# eElements.net
KiCad netlist of a schematic drawn in Altium Designer
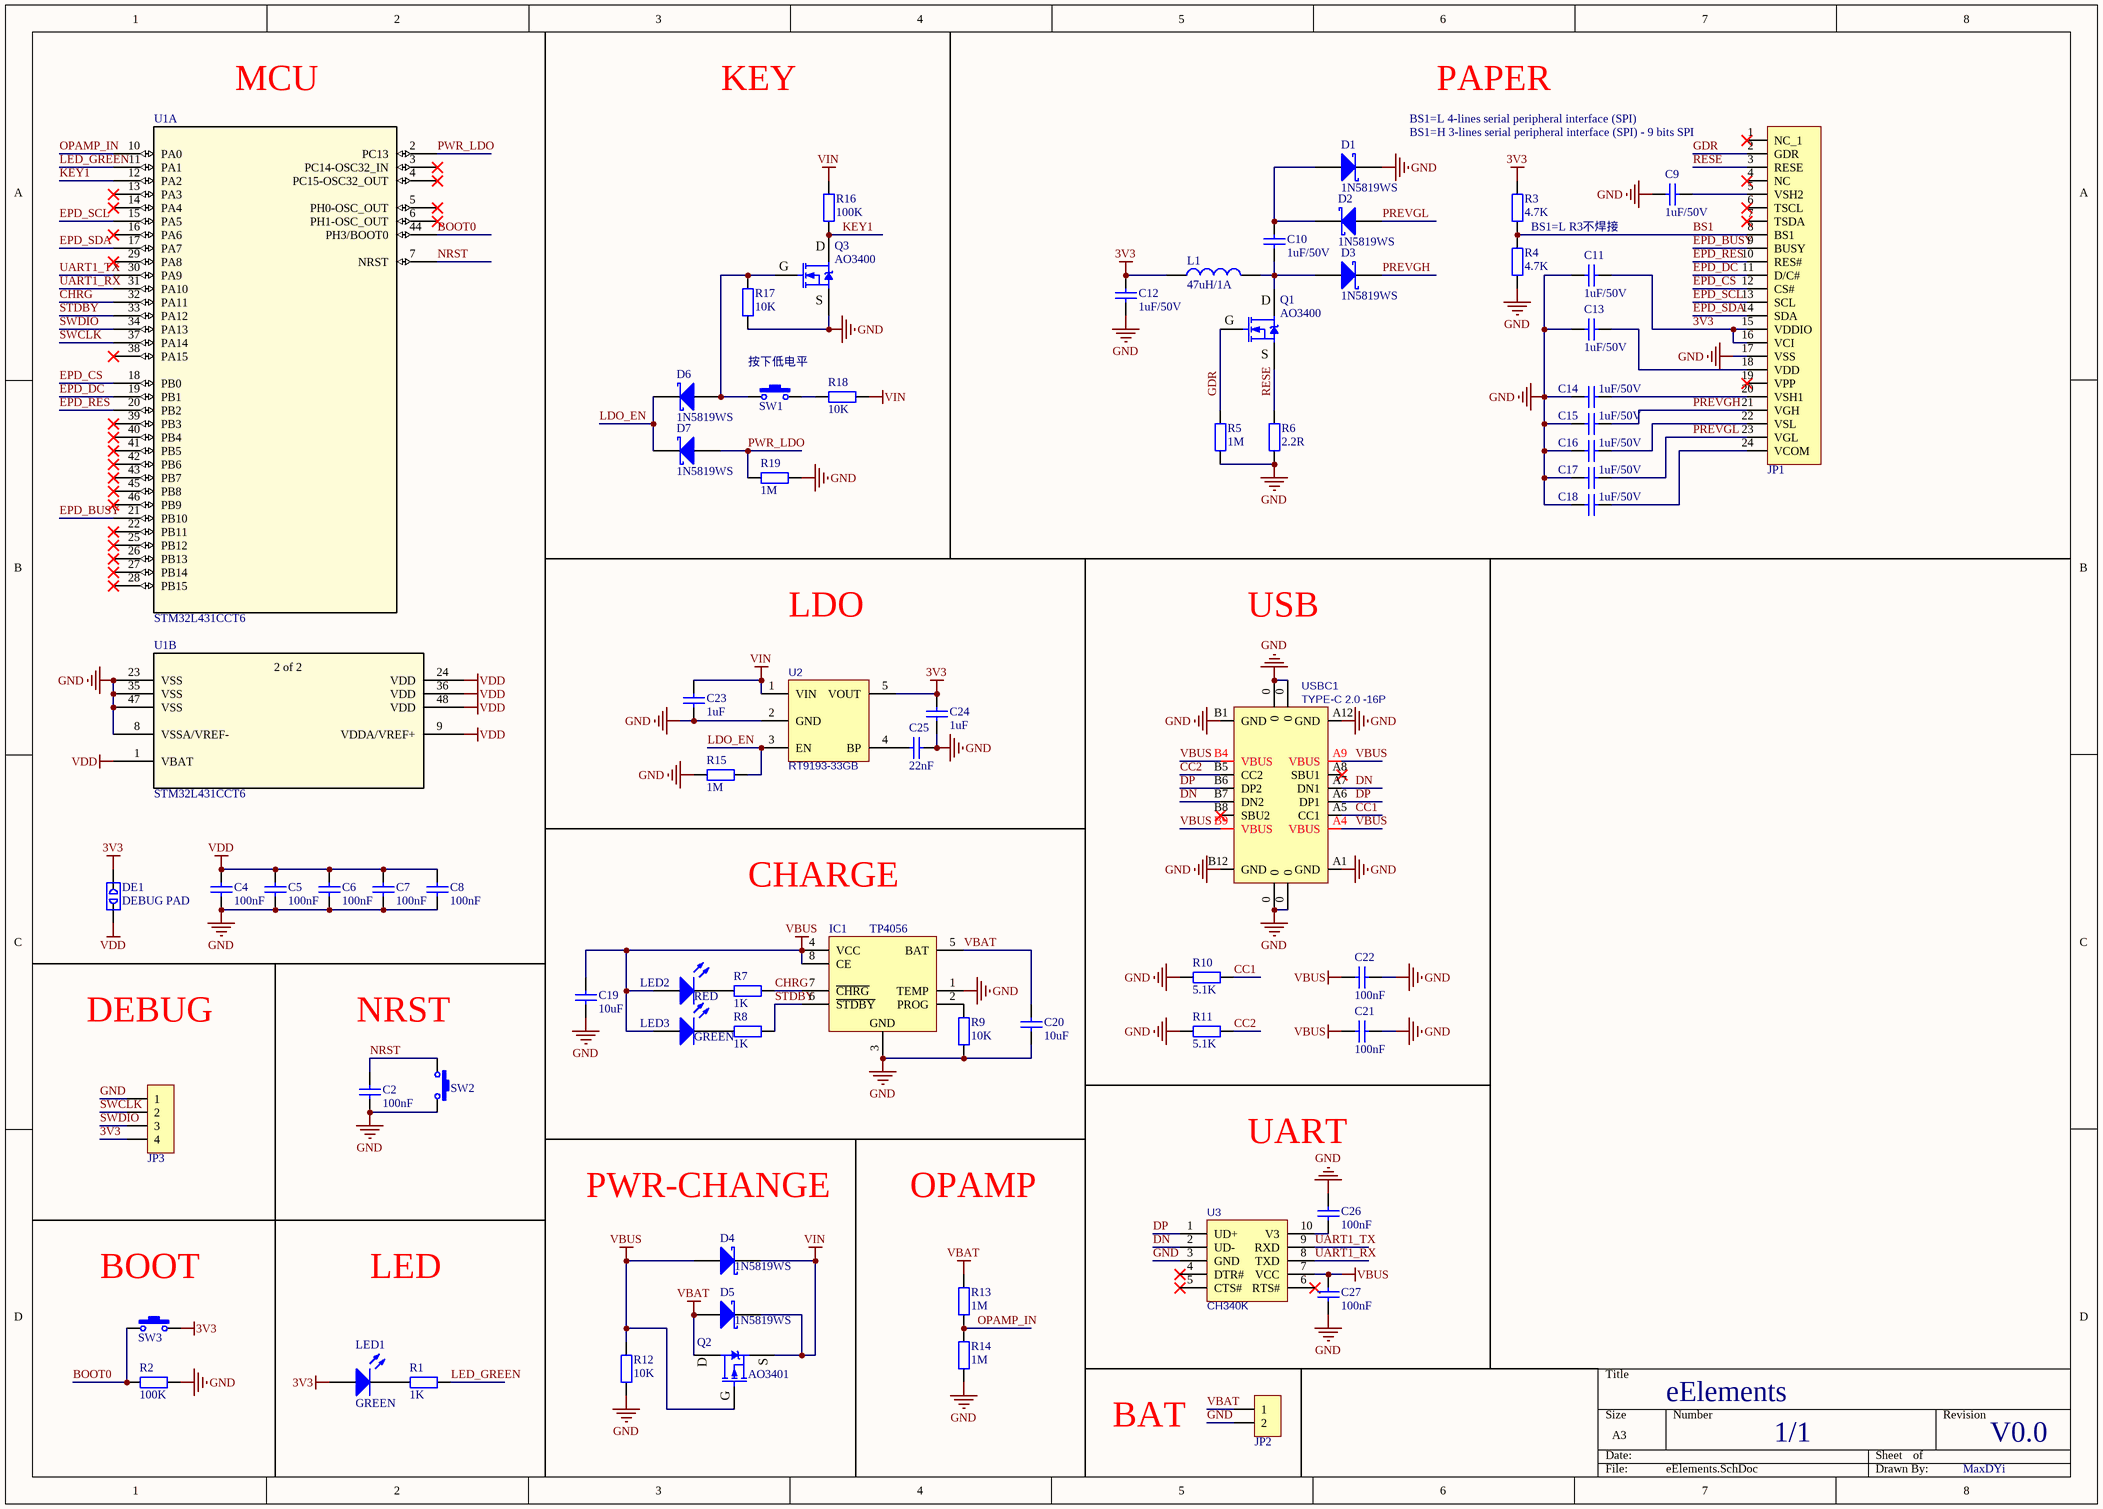
[diagram p0: eElements.SchDoc]

(export (version "E")
  (design (tool "Eeschema 10.0.6"))
  (components
    (comp (ref "C2")
      (value "100nF")
      (footprint "C0402_M")
      (description "贴片电容/MLCC电容")
      (libsource (lib "0.1 - 电阻-电容-电感-保险丝-晶振-晶体-磁珠-电位器-法拉电容-馈通电容") (part "C"))
    )
    (comp (ref "C4")
      (value "100nF")
      (footprint "C0402_M")
      (description "贴片电容/MLCC电容")
      (libsource (lib "0.1 - 电阻-电容-电感-保险丝-晶振-晶体-磁珠-电位器-法拉电容-馈通电容") (part "C"))
    )
    (comp (ref "C5")
      (value "100nF")
      (footprint "C0402_M")
      (description "贴片电容/MLCC电容")
      (libsource (lib "0.1 - 电阻-电容-电感-保险丝-晶振-晶体-磁珠-电位器-法拉电容-馈通电容") (part "C"))
    )
    (comp (ref "C6")
      (value "100nF")
      (footprint "C0402_M")
      (description "贴片电容/MLCC电容")
      (libsource (lib "0.1 - 电阻-电容-电感-保险丝-晶振-晶体-磁珠-电位器-法拉电容-馈通电容") (part "C"))
    )
    (comp (ref "C7")
      (value "100nF")
      (footprint "C0402_M")
      (description "贴片电容/MLCC电容")
      (libsource (lib "0.1 - 电阻-电容-电感-保险丝-晶振-晶体-磁珠-电位器-法拉电容-馈通电容") (part "C"))
    )
    (comp (ref "C8")
      (value "100nF")
      (footprint "C0402_M")
      (description "贴片电容/MLCC电容")
      (libsource (lib "0.1 - 电阻-电容-电感-保险丝-晶振-晶体-磁珠-电位器-法拉电容-馈通电容") (part "C"))
    )
    (comp (ref "C9")
      (value "1uF/50V")
      (footprint "C0402_M")
      (description "贴片电容/MLCC电容")
      (libsource (lib "0.1 - 电阻-电容-电感-保险丝-晶振-晶体-磁珠-电位器-法拉电容-馈通电容") (part "C"))
    )
    (comp (ref "C10")
      (value "1uF/50V")
      (footprint "C0402_M")
      (description "贴片电容/MLCC电容")
      (libsource (lib "0.1 - 电阻-电容-电感-保险丝-晶振-晶体-磁珠-电位器-法拉电容-馈通电容") (part "C"))
    )
    (comp (ref "C11")
      (value "1uF/50V")
      (footprint "C0402_M")
      (description "贴片电容/MLCC电容")
      (libsource (lib "0.1 - 电阻-电容-电感-保险丝-晶振-晶体-磁珠-电位器-法拉电容-馈通电容") (part "C"))
    )
    (comp (ref "C12")
      (value "1uF/50V")
      (footprint "C0402_M")
      (description "贴片电容/MLCC电容")
      (libsource (lib "0.1 - 电阻-电容-电感-保险丝-晶振-晶体-磁珠-电位器-法拉电容-馈通电容") (part "C"))
    )
    (comp (ref "C13")
      (value "1uF/50V")
      (footprint "C0402_M")
      (description "贴片电容/MLCC电容")
      (libsource (lib "0.1 - 电阻-电容-电感-保险丝-晶振-晶体-磁珠-电位器-法拉电容-馈通电容") (part "C"))
    )
    (comp (ref "C14")
      (value "1uF/50V")
      (footprint "C0402_M")
      (description "贴片电容/MLCC电容")
      (libsource (lib "0.1 - 电阻-电容-电感-保险丝-晶振-晶体-磁珠-电位器-法拉电容-馈通电容") (part "C"))
    )
    (comp (ref "C15")
      (value "1uF/50V")
      (footprint "C0402_M")
      (description "贴片电容/MLCC电容")
      (libsource (lib "0.1 - 电阻-电容-电感-保险丝-晶振-晶体-磁珠-电位器-法拉电容-馈通电容") (part "C"))
    )
    (comp (ref "C16")
      (value "1uF/50V")
      (footprint "C0402_M")
      (description "贴片电容/MLCC电容")
      (libsource (lib "0.1 - 电阻-电容-电感-保险丝-晶振-晶体-磁珠-电位器-法拉电容-馈通电容") (part "C"))
    )
    (comp (ref "C17")
      (value "1uF/50V")
      (footprint "C0402_M")
      (description "贴片电容/MLCC电容")
      (libsource (lib "0.1 - 电阻-电容-电感-保险丝-晶振-晶体-磁珠-电位器-法拉电容-馈通电容") (part "C"))
    )
    (comp (ref "C18")
      (value "1uF/50V")
      (footprint "C0402_M")
      (description "贴片电容/MLCC电容")
      (libsource (lib "0.1 - 电阻-电容-电感-保险丝-晶振-晶体-磁珠-电位器-法拉电容-馈通电容") (part "C"))
    )
    (comp (ref "C19")
      (value "10uF")
      (footprint "C0402_M")
      (description "贴片电容/MLCC电容")
      (libsource (lib "0.1 - 电阻-电容-电感-保险丝-晶振-晶体-磁珠-电位器-法拉电容-馈通电容") (part "C"))
    )
    (comp (ref "C20")
      (value "10uF")
      (footprint "C0402_M")
      (description "贴片电容/MLCC电容")
      (libsource (lib "0.1 - 电阻-电容-电感-保险丝-晶振-晶体-磁珠-电位器-法拉电容-馈通电容") (part "C"))
    )
    (comp (ref "C21")
      (value "100nF")
      (footprint "C0402_M")
      (description "贴片电容/MLCC电容")
      (libsource (lib "0.1 - 电阻-电容-电感-保险丝-晶振-晶体-磁珠-电位器-法拉电容-馈通电容") (part "C"))
    )
    (comp (ref "C22")
      (value "100nF")
      (footprint "C0402_M")
      (description "贴片电容/MLCC电容")
      (libsource (lib "0.1 - 电阻-电容-电感-保险丝-晶振-晶体-磁珠-电位器-法拉电容-馈通电容") (part "C"))
    )
    (comp (ref "C23")
      (value "1uF")
      (footprint "C0402_M")
      (description "贴片电容/MLCC电容")
      (libsource (lib "0.1 - 电阻-电容-电感-保险丝-晶振-晶体-磁珠-电位器-法拉电容-馈通电容") (part "C"))
    )
    (comp (ref "C24")
      (value "1uF")
      (footprint "C0402_M")
      (description "贴片电容/MLCC电容")
      (libsource (lib "0.1 - 电阻-电容-电感-保险丝-晶振-晶体-磁珠-电位器-法拉电容-馈通电容") (part "C"))
    )
    (comp (ref "C25")
      (value "22nF")
      (footprint "C0402_M")
      (description "贴片电容/MLCC电容")
      (libsource (lib "0.1 - 电阻-电容-电感-保险丝-晶振-晶体-磁珠-电位器-法拉电容-馈通电容") (part "C"))
    )
    (comp (ref "C26")
      (value "100nF")
      (footprint "C0402_M")
      (description "贴片电容/MLCC电容")
      (libsource (lib "0.1 - 电阻-电容-电感-保险丝-晶振-晶体-磁珠-电位器-法拉电容-馈通电容") (part "C"))
    )
    (comp (ref "C27")
      (value "100nF")
      (footprint "C0402_M")
      (description "贴片电容/MLCC电容")
      (libsource (lib "0.1 - 电阻-电容-电感-保险丝-晶振-晶体-磁珠-电位器-法拉电容-馈通电容") (part "C"))
    )
    (comp (ref "D1")
      (value "1N5819WS")
      (footprint "SOD-323")
      (description "肖特基二极管")
      (libsource (lib "0.2 - 二极管-TVS-ESD-整流桥-放电管") (part "1N5819"))
    )
    (comp (ref "D2")
      (value "1N5819WS")
      (footprint "SOD-323")
      (description "肖特基二极管")
      (libsource (lib "0.2 - 二极管-TVS-ESD-整流桥-放电管") (part "1N5819"))
    )
    (comp (ref "D3")
      (value "1N5819WS")
      (footprint "SOD-323")
      (description "肖特基二极管")
      (libsource (lib "0.2 - 二极管-TVS-ESD-整流桥-放电管") (part "1N5819"))
    )
    (comp (ref "D4")
      (value "1N5819WS")
      (footprint "SOD-323")
      (description "肖特基二极管")
      (libsource (lib "0.2 - 二极管-TVS-ESD-整流桥-放电管") (part "1N5819"))
    )
    (comp (ref "D5")
      (value "1N5819WS")
      (footprint "SOD-323")
      (description "肖特基二极管")
      (libsource (lib "0.2 - 二极管-TVS-ESD-整流桥-放电管") (part "1N5819"))
    )
    (comp (ref "D6")
      (value "1N5819WS")
      (footprint "SOD-323")
      (description "肖特基二极管")
      (libsource (lib "0.2 - 二极管-TVS-ESD-整流桥-放电管") (part "1N5819"))
    )
    (comp (ref "D7")
      (value "1N5819WS")
      (footprint "SOD-323")
      (description "肖特基二极管")
      (libsource (lib "0.2 - 二极管-TVS-ESD-整流桥-放电管") (part "1N5819"))
    )
    (comp (ref "DE1")
      (value "DEBUG PAD")
      (footprint "DEBUG_B")
      (description "调试断点焊盘")
      (libsource (lib "0.5 - 按键_开关_蜂鸣器_电池_测试点_Mark点_铜柱") (part "DEBUG"))
    )
    (comp (ref "IC1")
      (value "TP4056")
      (footprint "SOIC-8_EP")
      (description "锂电池充电管理")
      (libsource (lib "0.7 - 电源类芯片") (part "TP4056"))
    )
    (comp (ref "JP1")
      (value "CON-24P")
      (footprint "FPC0.5-WT-24P-上接")
      (description "2.54寸墨水屏24P连接器（上接点或上下接点24PIN的0.5mmFPC插座）")
      (libsource (lib "0.9 - 传感器-存储器-模块") (part "EPD-1.54"))
    )
    (comp (ref "JP2")
      (value "HDR-1X2")
      (footprint "MX1.25-W-2P")
      (description "2P连接器")
      (libsource (lib "5.1 - 1.25mm连接器(FPC1.25_GH1.25_MX1.25)") (part "Header 2"))
    )
    (comp (ref "JP3")
      (value "HDR-1X4")
      (footprint "HDR1.27-LI-4P")
      (description "4P连接器")
      (libsource (lib "5.2 - 1.27mm连接器(1.27排针排母)") (part "Header 4"))
    )
    (comp (ref "L1")
      (value "47uH/1A")
      (footprint "SWPA4030")
      (description "贴片小功率电感")
      (libsource (lib "0.1 - 电阻-电容-电感-保险丝-晶振-晶体-磁珠-电位器-法拉电容-馈通电容") (part "L"))
    )
    (comp (ref "LED1")
      (value "GREEN")
      (footprint "LED0603_R")
      (description "贴片LED")
      (libsource (lib "0.3 - LED发光二极管-IR二极管_接收管-光耦") (part "LED"))
    )
    (comp (ref "LED2")
      (value "RED")
      (footprint "LED0603_R")
      (description "贴片LED")
      (libsource (lib "0.3 - LED发光二极管-IR二极管_接收管-光耦") (part "LED"))
    )
    (comp (ref "LED3")
      (value "GREEN")
      (footprint "LED0603_R")
      (description "贴片LED")
      (libsource (lib "0.3 - LED发光二极管-IR二极管_接收管-光耦") (part "LED"))
    )
    (comp (ref "Q1")
      (value "AO3400")
      (footprint "SOT23-3N")
      (description "N沟道 30V/4.2A")
      (libsource (lib "0.4 - 三极管-场效应管-可控硅") (part "AO3400"))
    )
    (comp (ref "Q2")
      (value "AO3401")
      (footprint "SOT23-3N")
      (description "P沟道 30V/4.2A")
      (libsource (lib "0.4 - 三极管-场效应管-可控硅") (part "AO3401"))
    )
    (comp (ref "Q3")
      (value "AO3400")
      (footprint "SOT23-3N")
      (description "N沟道 30V/4.2A")
      (libsource (lib "0.4 - 三极管-场效应管-可控硅") (part "AO3400"))
    )
    (comp (ref "R1")
      (value "1K")
      (footprint "R0402_M")
      (description "贴片电阻")
      (libsource (lib "0.1 - 电阻-电容-电感-保险丝-晶振-晶体-磁珠-电位器-法拉电容-馈通电容") (part "R"))
    )
    (comp (ref "R2")
      (value "100K")
      (footprint "R0402_M")
      (description "贴片电阻")
      (libsource (lib "0.1 - 电阻-电容-电感-保险丝-晶振-晶体-磁珠-电位器-法拉电容-馈通电容") (part "R"))
    )
    (comp (ref "R3")
      (value "4.7K")
      (footprint "R0402_M")
      (description "贴片电阻")
      (libsource (lib "0.1 - 电阻-电容-电感-保险丝-晶振-晶体-磁珠-电位器-法拉电容-馈通电容") (part "R"))
    )
    (comp (ref "R4")
      (value "4.7K")
      (footprint "R0402_M")
      (description "贴片电阻")
      (libsource (lib "0.1 - 电阻-电容-电感-保险丝-晶振-晶体-磁珠-电位器-法拉电容-馈通电容") (part "R"))
    )
    (comp (ref "R5")
      (value "1M")
      (footprint "R0402_M")
      (description "贴片电阻")
      (libsource (lib "0.1 - 电阻-电容-电感-保险丝-晶振-晶体-磁珠-电位器-法拉电容-馈通电容") (part "R"))
    )
    (comp (ref "R6")
      (value "2.2R")
      (footprint "R0603_M")
      (description "贴片电阻")
      (libsource (lib "0.1 - 电阻-电容-电感-保险丝-晶振-晶体-磁珠-电位器-法拉电容-馈通电容") (part "R"))
    )
    (comp (ref "R7")
      (value "1K")
      (footprint "R0402_M")
      (description "贴片电阻")
      (libsource (lib "0.1 - 电阻-电容-电感-保险丝-晶振-晶体-磁珠-电位器-法拉电容-馈通电容") (part "R"))
    )
    (comp (ref "R8")
      (value "1K")
      (footprint "R0402_M")
      (description "贴片电阻")
      (libsource (lib "0.1 - 电阻-电容-电感-保险丝-晶振-晶体-磁珠-电位器-法拉电容-馈通电容") (part "R"))
    )
    (comp (ref "R9")
      (value "10K")
      (footprint "R0402_M")
      (description "贴片电阻")
      (libsource (lib "0.1 - 电阻-电容-电感-保险丝-晶振-晶体-磁珠-电位器-法拉电容-馈通电容") (part "R"))
    )
    (comp (ref "R10")
      (value "5.1K")
      (footprint "R0402_M")
      (description "贴片电阻")
      (libsource (lib "0.1 - 电阻-电容-电感-保险丝-晶振-晶体-磁珠-电位器-法拉电容-馈通电容") (part "R"))
    )
    (comp (ref "R11")
      (value "5.1K")
      (footprint "R0402_M")
      (description "贴片电阻")
      (libsource (lib "0.1 - 电阻-电容-电感-保险丝-晶振-晶体-磁珠-电位器-法拉电容-馈通电容") (part "R"))
    )
    (comp (ref "R12")
      (value "10K")
      (footprint "R0402_M")
      (description "贴片电阻")
      (libsource (lib "0.1 - 电阻-电容-电感-保险丝-晶振-晶体-磁珠-电位器-法拉电容-馈通电容") (part "R"))
    )
    (comp (ref "R13")
      (value "1M")
      (footprint "R0402_M")
      (description "贴片电阻")
      (libsource (lib "0.1 - 电阻-电容-电感-保险丝-晶振-晶体-磁珠-电位器-法拉电容-馈通电容") (part "R"))
    )
    (comp (ref "R14")
      (value "1M")
      (footprint "R0402_M")
      (description "贴片电阻")
      (libsource (lib "0.1 - 电阻-电容-电感-保险丝-晶振-晶体-磁珠-电位器-法拉电容-馈通电容") (part "R"))
    )
    (comp (ref "R15")
      (value "1M")
      (footprint "R0402_M")
      (description "贴片电阻")
      (libsource (lib "0.1 - 电阻-电容-电感-保险丝-晶振-晶体-磁珠-电位器-法拉电容-馈通电容") (part "R"))
    )
    (comp (ref "R16")
      (value "100K")
      (footprint "R0402_M")
      (description "贴片电阻")
      (libsource (lib "0.1 - 电阻-电容-电感-保险丝-晶振-晶体-磁珠-电位器-法拉电容-馈通电容") (part "R"))
    )
    (comp (ref "R17")
      (value "10K")
      (footprint "R0402_M")
      (description "贴片电阻")
      (libsource (lib "0.1 - 电阻-电容-电感-保险丝-晶振-晶体-磁珠-电位器-法拉电容-馈通电容") (part "R"))
    )
    (comp (ref "R18")
      (value "10K")
      (footprint "R0402_M")
      (description "贴片电阻")
      (libsource (lib "0.1 - 电阻-电容-电感-保险丝-晶振-晶体-磁珠-电位器-法拉电容-馈通电容") (part "R"))
    )
    (comp (ref "R19")
      (value "1M")
      (footprint "R0402_M")
      (description "贴片电阻")
      (libsource (lib "0.1 - 电阻-电容-电感-保险丝-晶振-晶体-磁珠-电位器-法拉电容-馈通电容") (part "R"))
    )
    (comp (ref "SW1")
      (value "3x6x5")
      (footprint "SW 3*6*4.3-S-W")
      (description "微动开关")
      (libsource (lib "0.5 - 按键_开关_蜂鸣器_电池_测试点_Mark点_铜柱") (part "SW-PB"))
    )
    (comp (ref "SW2")
      (value "3x6x5")
      (footprint "SW SMD-3*6*2.5")
      (description "微动开关")
      (libsource (lib "0.5 - 按键_开关_蜂鸣器_电池_测试点_Mark点_铜柱") (part "SW-PB"))
    )
    (comp (ref "SW3")
      (value "3x6x5")
      (footprint "SW SMD-3*6*2.5")
      (description "微动开关")
      (libsource (lib "0.5 - 按键_开关_蜂鸣器_电池_测试点_Mark点_铜柱") (part "SW-PB"))
    )
    (comp (ref "U1")
      (value "STM32L431CCT6")
      (footprint "LQFP48_M")
      (description "Ultra-low-power with FPU Arm Cortex-M4 MCU 80 MHz with 256 Kbytes of Flash memory")
      (libsource (lib "3.0 - STM32L0-L1-L4系列单片机") (part "STM32L431CCT6"))
    )
    (comp (ref "U2")
      (value "RT9193-33GB")
      (footprint "SOT-23-5")
      (description "LDO 3.3V/0.3A")
      (libsource (lib "0.7 - 电源类芯片") (part "RT9193-33GB"))
    )
    (comp (ref "U3")
      (value "CH340K")
      (footprint "SOP10_M")
      (description "USB转串口芯片, 内置晶振")
      (libsource (lib "0.8 - 常见芯片") (part "CH340K"))
    )
    (comp (ref "USBC1")
      (value "TYPE-C 2.0 -16P")
      (footprint "USB-C-SMD_16P")
      (description "USB2.0_Type-C_16Pin母座")
      (libsource (lib "0.6 - 电源_音频_USB Type-C_HDMI_XT60_5557_D-SUB_RJ45_SD-TF_SIM插座") (part "USB2.0_Type-C_16Pin"))
    )
  )
  (nets
    (net (code "1") (name "/BOOT0") (class "Default")
      (node (ref "R2") (pin "1") (pinfunction "1_1") (pintype "passive"))
      (node (ref "SW3") (pin "1") (pinfunction "1_1") (pintype "passive"))
      (node (ref "U1") (pin "44") (pinfunction "PH3/BOOT0_44") (pintype "bidirectional"))
    )
    (net (code "2") (name "/BS1") (class "Default")
      (node (ref "JP1") (pin "8") (pinfunction "BS1_8") (pintype "passive"))
      (node (ref "R3") (pin "1") (pinfunction "1_1") (pintype "passive"))
      (node (ref "R4") (pin "2") (pinfunction "2_2") (pintype "passive"))
    )
    (net (code "3") (name "/CC1") (class "Default")
      (node (ref "R10") (pin "1") (pinfunction "1_1") (pintype "passive"))
      (node (ref "USBC1") (pin "A5") (pinfunction "CC1_A5") (pintype "passive"))
    )
    (net (code "4") (name "/CC2") (class "Default")
      (node (ref "R11") (pin "1") (pinfunction "1_1") (pintype "passive"))
      (node (ref "USBC1") (pin "B5") (pinfunction "CC2_B5") (pintype "passive"))
    )
    (net (code "5") (name "/CHRG") (class "Default")
      (node (ref "IC1") (pin "7") (pinfunction "~{CHRG}_7") (pintype "passive"))
      (node (ref "R7") (pin "1") (pinfunction "1_1") (pintype "passive"))
      (node (ref "U1") (pin "32") (pinfunction "PA11_32") (pintype "bidirectional"))
    )
    (net (code "6") (name "/DN") (class "Default")
      (node (ref "U3") (pin "2") (pinfunction "UD-_2") (pintype "passive"))
      (node (ref "USBC1") (pin "A7") (pinfunction "DN1_A7") (pintype "passive"))
      (node (ref "USBC1") (pin "B7") (pinfunction "DN2_B7") (pintype "passive"))
    )
    (net (code "7") (name "/DP") (class "Default")
      (node (ref "U3") (pin "1") (pinfunction "UD+_1") (pintype "passive"))
      (node (ref "USBC1") (pin "A6") (pinfunction "DP1_A6") (pintype "passive"))
      (node (ref "USBC1") (pin "B6") (pinfunction "DP2_B6") (pintype "passive"))
    )
    (net (code "8") (name "/EPD_BUSY") (class "Default")
      (node (ref "JP1") (pin "9") (pinfunction "BUSY_9") (pintype "passive"))
      (node (ref "U1") (pin "21") (pinfunction "PB10_21") (pintype "bidirectional"))
    )
    (net (code "9") (name "/EPD_CS") (class "Default")
      (node (ref "JP1") (pin "12") (pinfunction "CS#_12") (pintype "passive"))
      (node (ref "U1") (pin "18") (pinfunction "PB0_18") (pintype "bidirectional"))
    )
    (net (code "10") (name "/EPD_DC") (class "Default")
      (node (ref "JP1") (pin "11") (pinfunction "D/C#_11") (pintype "passive"))
      (node (ref "U1") (pin "19") (pinfunction "PB1_19") (pintype "bidirectional"))
    )
    (net (code "11") (name "/EPD_RES") (class "Default")
      (node (ref "JP1") (pin "10") (pinfunction "RES#_10") (pintype "passive"))
      (node (ref "U1") (pin "20") (pinfunction "PB2_20") (pintype "bidirectional"))
    )
    (net (code "12") (name "/EPD_SCL") (class "Default")
      (node (ref "JP1") (pin "13") (pinfunction "SCL_13") (pintype "passive"))
      (node (ref "U1") (pin "15") (pinfunction "PA5_15") (pintype "bidirectional"))
    )
    (net (code "13") (name "/EPD_SDA") (class "Default")
      (node (ref "JP1") (pin "14") (pinfunction "SDA_14") (pintype "passive"))
      (node (ref "U1") (pin "17") (pinfunction "PA7_17") (pintype "bidirectional"))
    )
    (net (code "14") (name "/GDR") (class "Default")
      (node (ref "JP1") (pin "2") (pinfunction "GDR_2") (pintype "passive"))
      (node (ref "Q1") (pin "1") (pinfunction "G_1") (pintype "passive"))
      (node (ref "R5") (pin "2") (pinfunction "2_2") (pintype "passive"))
    )
    (net (code "15") (name "/KEY1") (class "Default")
      (node (ref "Q3") (pin "3") (pinfunction "D_3") (pintype "passive"))
      (node (ref "R16") (pin "1") (pinfunction "1_1") (pintype "passive"))
      (node (ref "U1") (pin "12") (pinfunction "PA2_12") (pintype "bidirectional"))
    )
    (net (code "16") (name "/LDO_EN") (class "Default")
      (node (ref "D6") (pin "2") (pinfunction "K_2") (pintype "passive"))
      (node (ref "D7") (pin "2") (pinfunction "K_2") (pintype "passive"))
      (node (ref "R15") (pin "1") (pinfunction "1_1") (pintype "passive"))
      (node (ref "U2") (pin "3") (pinfunction "EN_3") (pintype "passive"))
    )
    (net (code "17") (name "/LED_GREEN") (class "Default")
      (node (ref "R1") (pin "1") (pinfunction "1_1") (pintype "passive"))
      (node (ref "U1") (pin "11") (pinfunction "PA1_11") (pintype "bidirectional"))
    )
    (net (code "18") (name "/NRST") (class "Default")
      (node (ref "C2") (pin "2") (pinfunction "2_2") (pintype "passive"))
      (node (ref "SW2") (pin "1") (pinfunction "1_1") (pintype "passive"))
      (node (ref "U1") (pin "7") (pinfunction "NRST_7") (pintype "bidirectional"))
    )
    (net (code "19") (name "/OPAMP_IN") (class "Default")
      (node (ref "R13") (pin "1") (pinfunction "1_1") (pintype "passive"))
      (node (ref "R14") (pin "2") (pinfunction "2_2") (pintype "passive"))
      (node (ref "U1") (pin "10") (pinfunction "PA0_10") (pintype "bidirectional"))
    )
    (net (code "20") (name "/PREVGH") (class "Default")
      (node (ref "C15") (pin "2") (pinfunction "2_2") (pintype "passive"))
      (node (ref "D3") (pin "2") (pinfunction "K_2") (pintype "passive"))
      (node (ref "JP1") (pin "21") (pinfunction "VGH_21") (pintype "passive"))
    )
    (net (code "21") (name "/PREVGL") (class "Default")
      (node (ref "C17") (pin "2") (pinfunction "2_2") (pintype "passive"))
      (node (ref "D2") (pin "1") (pinfunction "A_1") (pintype "passive"))
      (node (ref "JP1") (pin "23") (pinfunction "VGL_23") (pintype "passive"))
    )
    (net (code "22") (name "/PWR_LDO") (class "Default")
      (node (ref "D7") (pin "1") (pinfunction "A_1") (pintype "passive"))
      (node (ref "R19") (pin "2") (pinfunction "2_2") (pintype "passive"))
      (node (ref "U1") (pin "2") (pinfunction "PC13_2") (pintype "bidirectional"))
    )
    (net (code "23") (name "/RESE") (class "Default")
      (node (ref "JP1") (pin "3") (pinfunction "RESE_3") (pintype "passive"))
      (node (ref "Q1") (pin "2") (pinfunction "S_2") (pintype "passive"))
      (node (ref "R6") (pin "2") (pinfunction "2_2") (pintype "passive"))
    )
    (net (code "24") (name "/STDBY") (class "Default")
      (node (ref "IC1") (pin "6") (pinfunction "~{STDBY}_6") (pintype "passive"))
      (node (ref "R8") (pin "1") (pinfunction "1_1") (pintype "passive"))
      (node (ref "U1") (pin "33") (pinfunction "PA12_33") (pintype "bidirectional"))
    )
    (net (code "25") (name "/SWCLK") (class "Default")
      (node (ref "JP3") (pin "2") (pinfunction "2_2") (pintype "passive"))
      (node (ref "U1") (pin "37") (pinfunction "PA14_37") (pintype "bidirectional"))
    )
    (net (code "26") (name "/SWDIO") (class "Default")
      (node (ref "JP3") (pin "3") (pinfunction "3_3") (pintype "passive"))
      (node (ref "U1") (pin "34") (pinfunction "PA13_34") (pintype "bidirectional"))
    )
    (net (code "27") (name "/UART1_RX") (class "Default")
      (node (ref "U1") (pin "31") (pinfunction "PA10_31") (pintype "bidirectional"))
      (node (ref "U3") (pin "8") (pinfunction "TXD_8") (pintype "passive"))
    )
    (net (code "28") (name "/UART1_TX") (class "Default")
      (node (ref "U1") (pin "30") (pinfunction "PA9_30") (pintype "bidirectional"))
      (node (ref "U3") (pin "9") (pinfunction "RXD_9") (pintype "passive"))
    )
    (net (code "29") (name "3V3") (class "Default")
      (node (ref "C11") (pin "2") (pinfunction "2_2") (pintype "passive"))
      (node (ref "C12") (pin "2") (pinfunction "2_2") (pintype "passive"))
      (node (ref "C24") (pin "2") (pinfunction "2_2") (pintype "passive"))
      (node (ref "DE1") (pin "1") (pinfunction "1_1") (pintype "passive"))
      (node (ref "JP1") (pin "15") (pinfunction "VDDIO_15") (pintype "passive"))
      (node (ref "JP1") (pin "16") (pinfunction "VCI_16") (pintype "passive"))
      (node (ref "JP3") (pin "4") (pinfunction "4_4") (pintype "passive"))
      (node (ref "L1") (pin "1") (pinfunction "1_1") (pintype "passive"))
      (node (ref "LED1") (pin "1") (pinfunction "A_1") (pintype "passive"))
      (node (ref "R3") (pin "2") (pinfunction "2_2") (pintype "passive"))
      (node (ref "SW3") (pin "2") (pinfunction "2_2") (pintype "passive"))
      (node (ref "U2") (pin "5") (pinfunction "VOUT_5") (pintype "passive"))
    )
    (net (code "30") (name "GND") (class "Default")
      (node (ref "C11") (pin "1") (pinfunction "1_1") (pintype "passive"))
      (node (ref "C12") (pin "1") (pinfunction "1_1") (pintype "passive"))
      (node (ref "C13") (pin "1") (pinfunction "1_1") (pintype "passive"))
      (node (ref "C14") (pin "1") (pinfunction "1_1") (pintype "passive"))
      (node (ref "C15") (pin "1") (pinfunction "1_1") (pintype "passive"))
      (node (ref "C16") (pin "1") (pinfunction "1_1") (pintype "passive"))
      (node (ref "C17") (pin "1") (pinfunction "1_1") (pintype "passive"))
      (node (ref "C18") (pin "1") (pinfunction "1_1") (pintype "passive"))
      (node (ref "C19") (pin "1") (pinfunction "1_1") (pintype "passive"))
      (node (ref "C2") (pin "1") (pinfunction "1_1") (pintype "passive"))
      (node (ref "C20") (pin "1") (pinfunction "1_1") (pintype "passive"))
      (node (ref "C21") (pin "1") (pinfunction "1_1") (pintype "passive"))
      (node (ref "C22") (pin "1") (pinfunction "1_1") (pintype "passive"))
      (node (ref "C23") (pin "1") (pinfunction "1_1") (pintype "passive"))
      (node (ref "C24") (pin "1") (pinfunction "1_1") (pintype "passive"))
      (node (ref "C25") (pin "1") (pinfunction "1_1") (pintype "passive"))
      (node (ref "C26") (pin "2") (pinfunction "2_2") (pintype "passive"))
      (node (ref "C27") (pin "1") (pinfunction "1_1") (pintype "passive"))
      (node (ref "C4") (pin "1") (pinfunction "1_1") (pintype "passive"))
      (node (ref "C5") (pin "1") (pinfunction "1_1") (pintype "passive"))
      (node (ref "C6") (pin "1") (pinfunction "1_1") (pintype "passive"))
      (node (ref "C7") (pin "1") (pinfunction "1_1") (pintype "passive"))
      (node (ref "C8") (pin "1") (pinfunction "1_1") (pintype "passive"))
      (node (ref "C9") (pin "1") (pinfunction "1_1") (pintype "passive"))
      (node (ref "D1") (pin "2") (pinfunction "K_2") (pintype "passive"))
      (node (ref "IC1") (pin "1") (pinfunction "TEMP_1") (pintype "passive"))
      (node (ref "IC1") (pin "3") (pinfunction "GND_3") (pintype "passive"))
      (node (ref "JP1") (pin "17") (pinfunction "VSS_17") (pintype "passive"))
      (node (ref "JP2") (pin "2") (pinfunction "2_2") (pintype "passive"))
      (node (ref "JP3") (pin "1") (pinfunction "1_1") (pintype "passive"))
      (node (ref "Q3") (pin "2") (pinfunction "S_2") (pintype "passive"))
      (node (ref "R10") (pin "2") (pinfunction "2_2") (pintype "passive"))
      (node (ref "R11") (pin "2") (pinfunction "2_2") (pintype "passive"))
      (node (ref "R12") (pin "2") (pinfunction "2_2") (pintype "passive"))
      (node (ref "R14") (pin "1") (pinfunction "1_1") (pintype "passive"))
      (node (ref "R15") (pin "2") (pinfunction "2_2") (pintype "passive"))
      (node (ref "R17") (pin "1") (pinfunction "1_1") (pintype "passive"))
      (node (ref "R19") (pin "1") (pinfunction "1_1") (pintype "passive"))
      (node (ref "R2") (pin "2") (pinfunction "2_2") (pintype "passive"))
      (node (ref "R4") (pin "1") (pinfunction "1_1") (pintype "passive"))
      (node (ref "R5") (pin "1") (pinfunction "1_1") (pintype "passive"))
      (node (ref "R6") (pin "1") (pinfunction "1_1") (pintype "passive"))
      (node (ref "R9") (pin "1") (pinfunction "1_1") (pintype "passive"))
      (node (ref "SW2") (pin "2") (pinfunction "2_2") (pintype "passive"))
      (node (ref "U1") (pin "23") (pinfunction "VSS_23") (pintype "power_in"))
      (node (ref "U1") (pin "35") (pinfunction "VSS_35") (pintype "power_in"))
      (node (ref "U1") (pin "47") (pinfunction "VSS_47") (pintype "power_in"))
      (node (ref "U1") (pin "8") (pinfunction "VSSA/VREF-_8") (pintype "power_in"))
      (node (ref "U2") (pin "2") (pinfunction "GND_2") (pintype "passive"))
      (node (ref "U3") (pin "3") (pinfunction "GND_3") (pintype "passive"))
      (node (ref "USBC1") (pin "0") (pinfunction "0_0") (pintype "passive"))
      (node (ref "USBC1") (pin "A1") (pinfunction "GND_A1") (pintype "passive"))
      (node (ref "USBC1") (pin "A12") (pinfunction "GND_A12") (pintype "passive"))
      (node (ref "USBC1") (pin "B1") (pinfunction "GND_B1") (pintype "passive"))
      (node (ref "USBC1") (pin "B12") (pinfunction "GND_B12") (pintype "passive"))
    )
    (net (code "31") (name "Net-(D1-A)") (class "Default")
      (node (ref "C10") (pin "2") (pinfunction "2_2") (pintype "passive"))
      (node (ref "D1") (pin "1") (pinfunction "A_1") (pintype "passive"))
      (node (ref "D2") (pin "2") (pinfunction "K_2") (pintype "passive"))
    )
    (net (code "32") (name "Net-(D3-A)") (class "Default")
      (node (ref "C10") (pin "1") (pinfunction "1_1") (pintype "passive"))
      (node (ref "D3") (pin "1") (pinfunction "A_1") (pintype "passive"))
      (node (ref "L1") (pin "2") (pinfunction "2_2") (pintype "passive"))
      (node (ref "Q1") (pin "3") (pinfunction "D_3") (pintype "passive"))
    )
    (net (code "33") (name "Net-(D6-A)") (class "Default")
      (node (ref "D6") (pin "1") (pinfunction "A_1") (pintype "passive"))
      (node (ref "Q3") (pin "1") (pinfunction "G_1") (pintype "passive"))
      (node (ref "R17") (pin "2") (pinfunction "2_2") (pintype "passive"))
      (node (ref "SW1") (pin "1") (pinfunction "1_1") (pintype "passive"))
    )
    (net (code "34") (name "Net-(IC1-PROG)") (class "Default")
      (node (ref "IC1") (pin "2") (pinfunction "PROG_2") (pintype "passive"))
      (node (ref "R9") (pin "2") (pinfunction "2_2") (pintype "passive"))
    )
    (net (code "35") (name "Net-(JP1-VCOM)") (class "Default")
      (node (ref "C18") (pin "2") (pinfunction "2_2") (pintype "passive"))
      (node (ref "JP1") (pin "24") (pinfunction "VCOM_24") (pintype "passive"))
    )
    (net (code "36") (name "Net-(JP1-VDD)") (class "Default")
      (node (ref "C13") (pin "2") (pinfunction "2_2") (pintype "passive"))
      (node (ref "JP1") (pin "18") (pinfunction "VDD_18") (pintype "passive"))
    )
    (net (code "37") (name "Net-(JP1-VSH1)") (class "Default")
      (node (ref "C14") (pin "2") (pinfunction "2_2") (pintype "passive"))
      (node (ref "JP1") (pin "20") (pinfunction "VSH1_20") (pintype "passive"))
    )
    (net (code "38") (name "Net-(JP1-VSH2)") (class "Default")
      (node (ref "C9") (pin "2") (pinfunction "2_2") (pintype "passive"))
      (node (ref "JP1") (pin "5") (pinfunction "VSH2_5") (pintype "passive"))
    )
    (net (code "39") (name "Net-(JP1-VSL)") (class "Default")
      (node (ref "C16") (pin "2") (pinfunction "2_2") (pintype "passive"))
      (node (ref "JP1") (pin "22") (pinfunction "VSL_22") (pintype "passive"))
    )
    (net (code "40") (name "Net-(LED1-K)") (class "Default")
      (node (ref "LED1") (pin "2") (pinfunction "K_2") (pintype "passive"))
      (node (ref "R1") (pin "2") (pinfunction "2_2") (pintype "passive"))
    )
    (net (code "41") (name "Net-(LED2-K)") (class "Default")
      (node (ref "LED2") (pin "2") (pinfunction "K_2") (pintype "passive"))
      (node (ref "R7") (pin "2") (pinfunction "2_2") (pintype "passive"))
    )
    (net (code "42") (name "Net-(LED3-K)") (class "Default")
      (node (ref "LED3") (pin "2") (pinfunction "K_2") (pintype "passive"))
      (node (ref "R8") (pin "2") (pinfunction "2_2") (pintype "passive"))
    )
    (net (code "43") (name "Net-(R18-Pad2)") (class "Default")
      (node (ref "R18") (pin "2") (pinfunction "2_2") (pintype "passive"))
      (node (ref "SW1") (pin "2") (pinfunction "2_2") (pintype "passive"))
    )
    (net (code "44") (name "Net-(U2-BP)") (class "Default")
      (node (ref "C25") (pin "2") (pinfunction "2_2") (pintype "passive"))
      (node (ref "U2") (pin "4") (pinfunction "BP_4") (pintype "passive"))
    )
    (net (code "45") (name "Net-(U3-V3)") (class "Default")
      (node (ref "C26") (pin "1") (pinfunction "1_1") (pintype "passive"))
      (node (ref "U3") (pin "10") (pinfunction "V3_10") (pintype "passive"))
    )
    (net (code "46") (name "VBAT") (class "Default")
      (node (ref "C20") (pin "2") (pinfunction "2_2") (pintype "passive"))
      (node (ref "D5") (pin "1") (pinfunction "A_1") (pintype "passive"))
      (node (ref "IC1") (pin "5") (pinfunction "BAT_5") (pintype "passive"))
      (node (ref "JP2") (pin "1") (pinfunction "1_1") (pintype "passive"))
      (node (ref "Q2") (pin "3") (pinfunction "D_3") (pintype "passive"))
      (node (ref "R13") (pin "2") (pinfunction "2_2") (pintype "passive"))
    )
    (net (code "47") (name "VBUS") (class "Default")
      (node (ref "C19") (pin "2") (pinfunction "2_2") (pintype "passive"))
      (node (ref "C21") (pin "2") (pinfunction "2_2") (pintype "passive"))
      (node (ref "C22") (pin "2") (pinfunction "2_2") (pintype "passive"))
      (node (ref "C27") (pin "2") (pinfunction "2_2") (pintype "passive"))
      (node (ref "D4") (pin "1") (pinfunction "A_1") (pintype "passive"))
      (node (ref "IC1") (pin "4") (pinfunction "VCC_4") (pintype "passive"))
      (node (ref "IC1") (pin "8") (pinfunction "CE_8") (pintype "passive"))
      (node (ref "LED2") (pin "1") (pinfunction "A_1") (pintype "passive"))
      (node (ref "LED3") (pin "1") (pinfunction "A_1") (pintype "passive"))
      (node (ref "Q2") (pin "1") (pinfunction "G_1") (pintype "passive"))
      (node (ref "R12") (pin "1") (pinfunction "1_1") (pintype "passive"))
      (node (ref "U3") (pin "7") (pinfunction "VCC_7") (pintype "passive"))
      (node (ref "USBC1") (pin "A4") (pinfunction "VBUS_A4") (pintype "passive"))
      (node (ref "USBC1") (pin "A9") (pinfunction "VBUS_A9") (pintype "passive"))
      (node (ref "USBC1") (pin "B4") (pinfunction "VBUS_B4") (pintype "passive"))
      (node (ref "USBC1") (pin "B9") (pinfunction "VBUS_B9") (pintype "passive"))
    )
    (net (code "48") (name "VDD") (class "Default")
      (node (ref "C4") (pin "2") (pinfunction "2_2") (pintype "passive"))
      (node (ref "C5") (pin "2") (pinfunction "2_2") (pintype "passive"))
      (node (ref "C6") (pin "2") (pinfunction "2_2") (pintype "passive"))
      (node (ref "C7") (pin "2") (pinfunction "2_2") (pintype "passive"))
      (node (ref "C8") (pin "2") (pinfunction "2_2") (pintype "passive"))
      (node (ref "DE1") (pin "2") (pinfunction "2_2") (pintype "passive"))
      (node (ref "U1") (pin "1") (pinfunction "VBAT_1") (pintype "power_in"))
      (node (ref "U1") (pin "24") (pinfunction "VDD_24") (pintype "power_in"))
      (node (ref "U1") (pin "36") (pinfunction "VDD_36") (pintype "power_in"))
      (node (ref "U1") (pin "48") (pinfunction "VDD_48") (pintype "power_in"))
      (node (ref "U1") (pin "9") (pinfunction "VDDA/VREF+_9") (pintype "power_in"))
    )
    (net (code "49") (name "VIN") (class "Default")
      (node (ref "C23") (pin "2") (pinfunction "2_2") (pintype "passive"))
      (node (ref "D4") (pin "2") (pinfunction "K_2") (pintype "passive"))
      (node (ref "D5") (pin "2") (pinfunction "K_2") (pintype "passive"))
      (node (ref "Q2") (pin "2") (pinfunction "S_2") (pintype "passive"))
      (node (ref "R16") (pin "2") (pinfunction "2_2") (pintype "passive"))
      (node (ref "R18") (pin "1") (pinfunction "1_1") (pintype "passive"))
      (node (ref "U2") (pin "1") (pinfunction "VIN_1") (pintype "passive"))
    )
    (net (code "50") (name "unconnected-(JP1-NC-Pad4)") (class "Default")
      (node (ref "JP1") (pin "4") (pinfunction "NC_4") (pintype "passive+no_connect"))
    )
    (net (code "51") (name "unconnected-(JP1-NC_1-Pad1)") (class "Default")
      (node (ref "JP1") (pin "1") (pinfunction "NC_1_1") (pintype "passive+no_connect"))
    )
    (net (code "52") (name "unconnected-(JP1-TSCL-Pad6)") (class "Default")
      (node (ref "JP1") (pin "6") (pinfunction "TSCL_6") (pintype "passive+no_connect"))
    )
    (net (code "53") (name "unconnected-(JP1-TSDA-Pad7)") (class "Default")
      (node (ref "JP1") (pin "7") (pinfunction "TSDA_7") (pintype "passive+no_connect"))
    )
    (net (code "54") (name "unconnected-(JP1-VPP-Pad19)") (class "Default")
      (node (ref "JP1") (pin "19") (pinfunction "VPP_19") (pintype "passive+no_connect"))
    )
    (net (code "55") (name "unconnected-(U1A-PA3-Pad13)") (class "Default")
      (node (ref "U1") (pin "13") (pinfunction "PA3_13") (pintype "bidirectional+no_connect"))
    )
    (net (code "56") (name "unconnected-(U1A-PA4-Pad14)") (class "Default")
      (node (ref "U1") (pin "14") (pinfunction "PA4_14") (pintype "bidirectional+no_connect"))
    )
    (net (code "57") (name "unconnected-(U1A-PA6-Pad16)") (class "Default")
      (node (ref "U1") (pin "16") (pinfunction "PA6_16") (pintype "bidirectional+no_connect"))
    )
    (net (code "58") (name "unconnected-(U1A-PA8-Pad29)") (class "Default")
      (node (ref "U1") (pin "29") (pinfunction "PA8_29") (pintype "bidirectional+no_connect"))
    )
    (net (code "59") (name "unconnected-(U1A-PA15-Pad38)") (class "Default")
      (node (ref "U1") (pin "38") (pinfunction "PA15_38") (pintype "bidirectional+no_connect"))
    )
    (net (code "60") (name "unconnected-(U1A-PB3-Pad39)") (class "Default")
      (node (ref "U1") (pin "39") (pinfunction "PB3_39") (pintype "bidirectional+no_connect"))
    )
    (net (code "61") (name "unconnected-(U1A-PB4-Pad40)") (class "Default")
      (node (ref "U1") (pin "40") (pinfunction "PB4_40") (pintype "bidirectional+no_connect"))
    )
    (net (code "62") (name "unconnected-(U1A-PB5-Pad41)") (class "Default")
      (node (ref "U1") (pin "41") (pinfunction "PB5_41") (pintype "bidirectional+no_connect"))
    )
    (net (code "63") (name "unconnected-(U1A-PB6-Pad42)") (class "Default")
      (node (ref "U1") (pin "42") (pinfunction "PB6_42") (pintype "bidirectional+no_connect"))
    )
    (net (code "64") (name "unconnected-(U1A-PB7-Pad43)") (class "Default")
      (node (ref "U1") (pin "43") (pinfunction "PB7_43") (pintype "bidirectional+no_connect"))
    )
    (net (code "65") (name "unconnected-(U1A-PB8-Pad45)") (class "Default")
      (node (ref "U1") (pin "45") (pinfunction "PB8_45") (pintype "bidirectional+no_connect"))
    )
    (net (code "66") (name "unconnected-(U1A-PB9-Pad46)") (class "Default")
      (node (ref "U1") (pin "46") (pinfunction "PB9_46") (pintype "bidirectional+no_connect"))
    )
    (net (code "67") (name "unconnected-(U1A-PB11-Pad22)") (class "Default")
      (node (ref "U1") (pin "22") (pinfunction "PB11_22") (pintype "bidirectional+no_connect"))
    )
    (net (code "68") (name "unconnected-(U1A-PB12-Pad25)") (class "Default")
      (node (ref "U1") (pin "25") (pinfunction "PB12_25") (pintype "bidirectional+no_connect"))
    )
    (net (code "69") (name "unconnected-(U1A-PB13-Pad26)") (class "Default")
      (node (ref "U1") (pin "26") (pinfunction "PB13_26") (pintype "bidirectional+no_connect"))
    )
    (net (code "70") (name "unconnected-(U1A-PB14-Pad27)") (class "Default")
      (node (ref "U1") (pin "27") (pinfunction "PB14_27") (pintype "bidirectional+no_connect"))
    )
    (net (code "71") (name "unconnected-(U1A-PB15-Pad28)") (class "Default")
      (node (ref "U1") (pin "28") (pinfunction "PB15_28") (pintype "bidirectional+no_connect"))
    )
    (net (code "72") (name "unconnected-(U1A-PC14-OSC32_IN-Pad3)") (class "Default")
      (node (ref "U1") (pin "3") (pinfunction "PC14-OSC32_IN_3") (pintype "bidirectional+no_connect"))
    )
    (net (code "73") (name "unconnected-(U1A-PC15-OSC32_OUT-Pad4)") (class "Default")
      (node (ref "U1") (pin "4") (pinfunction "PC15-OSC32_OUT_4") (pintype "bidirectional+no_connect"))
    )
    (net (code "74") (name "unconnected-(U1A-PH0-OSC_OUT-Pad5)") (class "Default")
      (node (ref "U1") (pin "5") (pinfunction "PH0-OSC_OUT_5") (pintype "bidirectional+no_connect"))
    )
    (net (code "75") (name "unconnected-(U1A-PH1-OSC_OUT-Pad6)") (class "Default")
      (node (ref "U1") (pin "6") (pinfunction "PH1-OSC_OUT_6") (pintype "bidirectional+no_connect"))
    )
    (net (code "76") (name "unconnected-(U3-CTS#-Pad5)") (class "Default")
      (node (ref "U3") (pin "5") (pinfunction "CTS#_5") (pintype "passive+no_connect"))
    )
    (net (code "77") (name "unconnected-(U3-DTR#-Pad4)") (class "Default")
      (node (ref "U3") (pin "4") (pinfunction "DTR#_4") (pintype "passive+no_connect"))
    )
    (net (code "78") (name "unconnected-(U3-RTS#-Pad6)") (class "Default")
      (node (ref "U3") (pin "6") (pinfunction "RTS#_6") (pintype "passive+no_connect"))
    )
    (net (code "79") (name "unconnected-(USBC1-SBU1-PadA8)") (class "Default")
      (node (ref "USBC1") (pin "A8") (pinfunction "SBU1_A8") (pintype "passive+no_connect"))
    )
    (net (code "80") (name "unconnected-(USBC1-SBU2-PadB8)") (class "Default")
      (node (ref "USBC1") (pin "B8") (pinfunction "SBU2_B8") (pintype "passive+no_connect"))
    )
  )
)
